# CH2_DIGITAL.net
KiCad netlist of a schematic drawn in Altium Designer
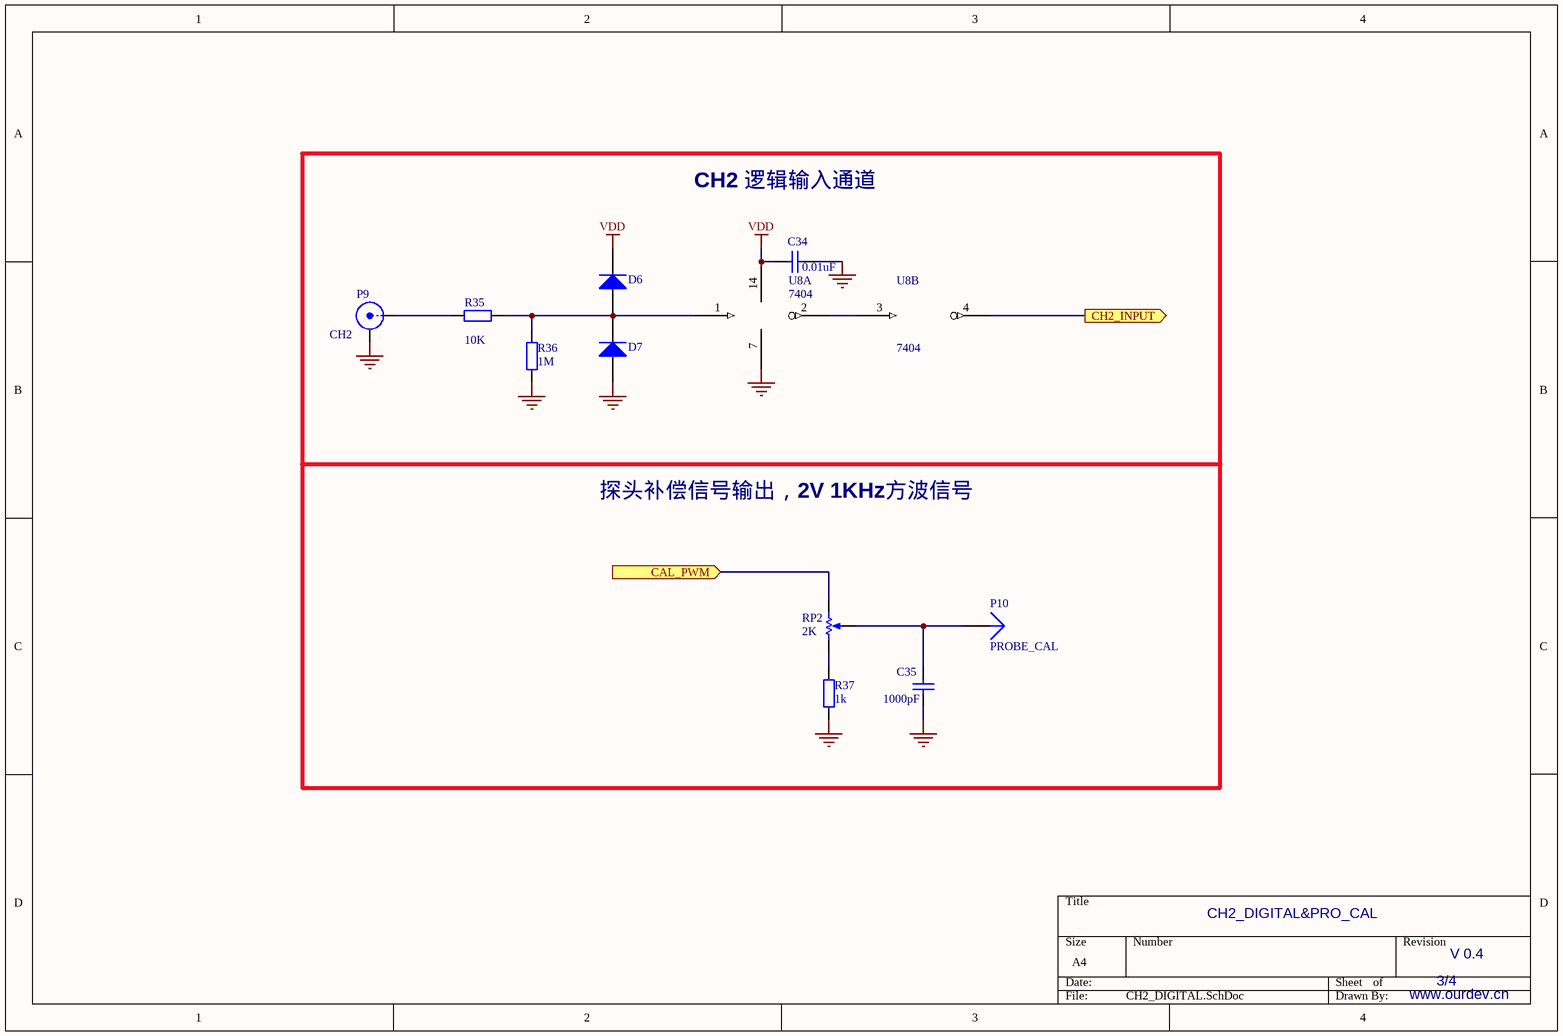
[diagram p0: CH2_DIGITAL.SchDoc]

(export (version "E")
  (design (tool "Eeschema 10.0.6"))
  (components
    (comp (ref "C34")
      (value "0.01uF")
      (footprint "CC2012-0805")
      (description "Capacitor")
      (fields (field (name "Comment") "Cap") (field (name "PUBLISHER") "Altium Limited"))
      (libsource (lib "Miscellaneous Devices") (part "Cap"))
    )
    (comp (ref "C35")
      (value "1000pF")
      (footprint "CC2012-0805")
      (description "Capacitor")
      (fields (field (name "Comment") "Cap") (field (name "PUBLISHER") "Altium Limited"))
      (libsource (lib "Miscellaneous Devices") (part "Cap"))
    )
    (comp (ref "D6")
      (value "Diode")
      (footprint "SMA")
      (description "Default Diode")
      (fields (field (name "PUBLISHER") "Altium Limited"))
      (libsource (lib "Miscellaneous Devices") (part "Diode"))
    )
    (comp (ref "D7")
      (value "Diode")
      (footprint "SMA")
      (description "Default Diode")
      (fields (field (name "PUBLISHER") "Altium Limited"))
      (libsource (lib "Miscellaneous Devices") (part "Diode"))
    )
    (comp (ref "P9")
      (value "CH2")
      (footprint "BNC_RA CON")
      (description "BNC Elbow Connector")
      (fields (field (name "PUBLISHER") "Altium Limited"))
      (libsource (lib "Miscellaneous Connectors") (part "BNC"))
    )
    (comp (ref "P10")
      (value "PROBE_CAL")
      (footprint "PIN1")
      (description "Plug")
      (fields (field (name "PUBLISHER") "Altium Limited"))
      (libsource (lib "Miscellaneous Connectors") (part "Plug"))
    )
    (comp (ref "R35")
      (value "10K")
      (footprint "CR2012-0805")
      (description "Resistor")
      (fields (field (name "Comment") "Res2") (field (name "PUBLISHER") "Altium Limited"))
      (libsource (lib "") (part "Res2_2"))
    )
    (comp (ref "R36")
      (value "1M")
      (footprint "CR2012-0805")
      (description "Resistor")
      (fields (field (name "Comment") "Res2") (field (name "PUBLISHER") "Altium Limited"))
      (libsource (lib "") (part "Res2_1"))
    )
    (comp (ref "R37")
      (value "1k")
      (footprint "CR2012-0805")
      (description "Resistor")
      (fields (field (name "Comment") "Res2") (field (name "PUBLISHER") "Altium Limited"))
      (libsource (lib "Miscellaneous Devices") (part "Res2"))
    )
    (comp (ref "RP2")
      (value "2K")
      (footprint "VR")
      (description "Potentiometer")
      (fields (field (name "PUBLISHER") "Altium Limited"))
      (libsource (lib "Miscellaneous Devices") (part "RPot"))
    )
    (comp (ref "U8") (value "7404") (footprint "SO-14") (libsource (lib "7404") (part "7404")))
  )
  (nets
    (net (code "1") (name "/CAL_PWM") (class "Default")
      (node (ref "RP2") (pin "3") (pinfunction "BOT_3") (pintype "passive"))
    )
    (net (code "2") (name "/CH2_INPUT") (class "Default") (node (ref "U8") (pin "4") (pintype "output")))
    (net (code "3") (name "GND") (class "Default")
      (node (ref "C34") (pin "1") (pinfunction "1_1") (pintype "passive"))
      (node (ref "C35") (pin "1") (pinfunction "1_1") (pintype "passive"))
      (node (ref "D7") (pin "1") (pinfunction "A_1") (pintype "passive"))
      (node (ref "P9") (pin "2") (pinfunction "Y_2") (pintype "passive"))
      (node (ref "R36") (pin "1") (pinfunction "1_1") (pintype "passive"))
      (node (ref "R37") (pin "2") (pinfunction "2_2") (pintype "passive"))
      (node (ref "U8") (pin "7") (pintype "power_in"))
    )
    (net (code "4") (name "Net-(D6-A)") (class "Default")
      (node (ref "D6") (pin "1") (pinfunction "A_1") (pintype "passive"))
      (node (ref "D7") (pin "2") (pinfunction "K_2") (pintype "passive"))
      (node (ref "R35") (pin "2") (pinfunction "2_2") (pintype "passive"))
      (node (ref "R36") (pin "2") (pinfunction "2_2") (pintype "passive"))
      (node (ref "U8") (pin "1") (pintype "input"))
    )
    (net (code "5") (name "Net-(P9-X)") (class "Default")
      (node (ref "P9") (pin "1") (pinfunction "X_1") (pintype "passive"))
      (node (ref "R35") (pin "1") (pinfunction "1_1") (pintype "passive"))
    )
    (net (code "6") (name "Net-(RP2-TAP)") (class "Default")
      (node (ref "C35") (pin "2") (pinfunction "2_2") (pintype "passive"))
      (node (ref "P10") (pin "1") (pinfunction "1_1") (pintype "passive"))
      (node (ref "RP2") (pin "2") (pinfunction "TAP_2") (pintype "passive"))
    )
    (net (code "7") (name "Net-(RP2-TOP)") (class "Default")
      (node (ref "R37") (pin "1") (pinfunction "1_1") (pintype "passive"))
      (node (ref "RP2") (pin "1") (pinfunction "TOP_1") (pintype "passive"))
    )
    (net (code "8") (name "Net-(U8-Pad2)") (class "Default")
      (node (ref "U8") (pin "2") (pintype "output"))
      (node (ref "U8") (pin "3") (pintype "input"))
    )
    (net (code "9") (name "VDD") (class "Default")
      (node (ref "C34") (pin "2") (pinfunction "2_2") (pintype "passive"))
      (node (ref "D6") (pin "2") (pinfunction "K_2") (pintype "passive"))
      (node (ref "U8") (pin "14") (pintype "power_in"))
    )
  )
)
